# controller_left_upper.net
KiCad netlist of a schematic drawn in EAGLE
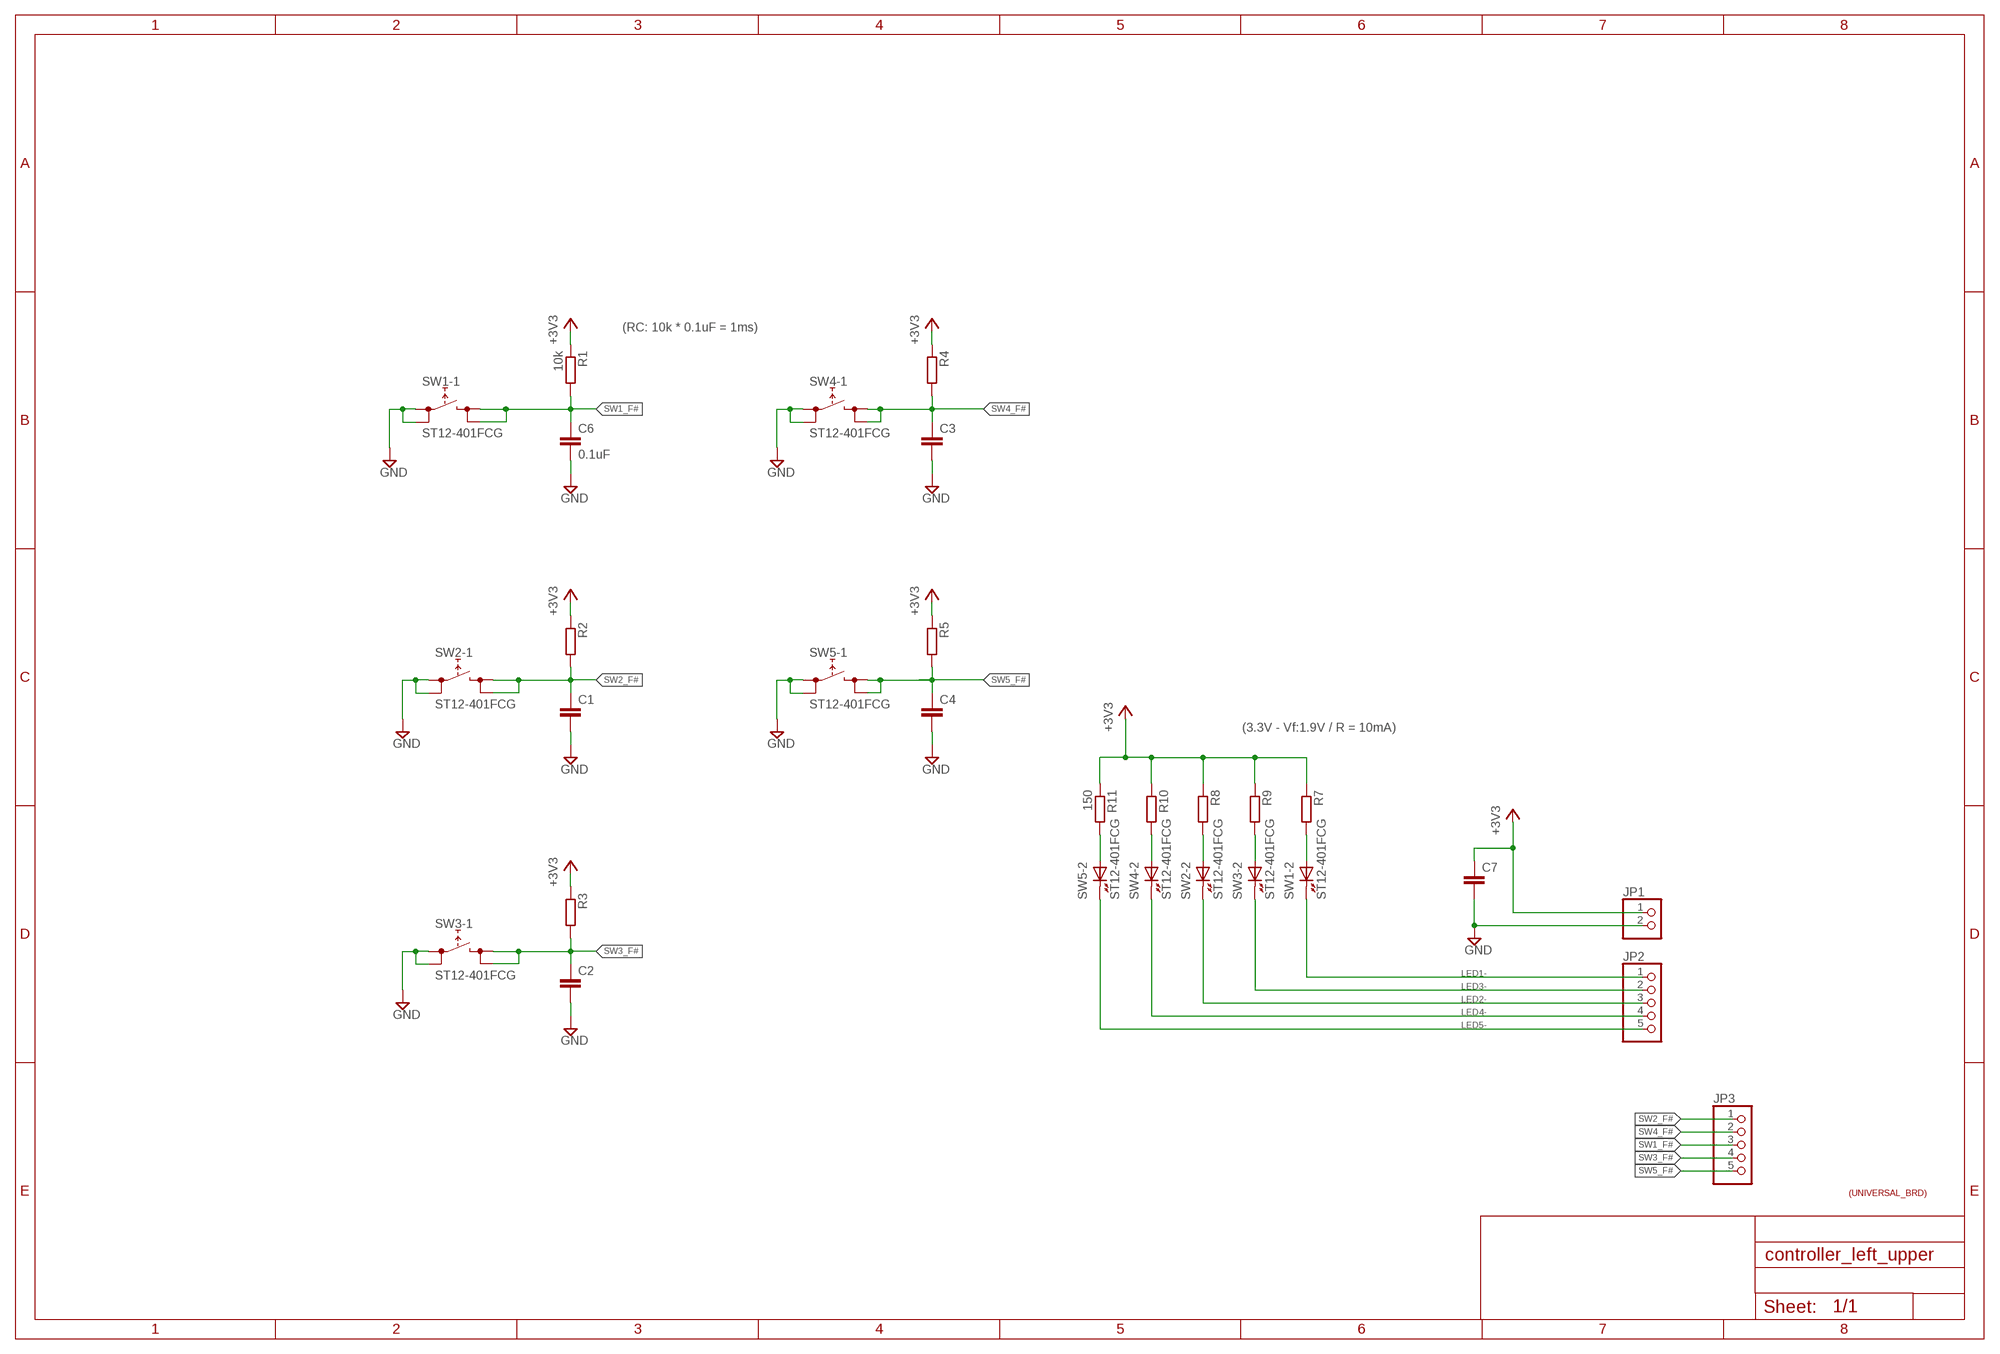
[diagram p0: schematic, sheet 1]

(export (version "E")
  (design (tool "Eeschema 10.0.6"))
  (components
    (comp (ref "C1")
      (value "C_DIP_2.54_1")
      (footprint "eagle-import:C_DIP2.54_1")
      (libsource (lib "eagle-import") (part "C_DIP_2.54_1"))
    )
    (comp (ref "C2")
      (value "C_DIP_2.54_1")
      (footprint "eagle-import:C_DIP2.54_1")
      (libsource (lib "eagle-import") (part "C_DIP_2.54_1"))
    )
    (comp (ref "C3")
      (value "C_DIP_2.54_1")
      (footprint "eagle-import:C_DIP2.54_1")
      (libsource (lib "eagle-import") (part "C_DIP_2.54_1"))
    )
    (comp (ref "C4")
      (value "C_DIP_2.54_1")
      (footprint "eagle-import:C_DIP2.54_1")
      (libsource (lib "eagle-import") (part "C_DIP_2.54_1"))
    )
    (comp (ref "C6")
      (value "0.1uF")
      (footprint "eagle-import:C_DIP2.54_1")
      (libsource (lib "eagle-import") (part "C_DIP_2.54_1"))
    )
    (comp (ref "C7")
      (value "C_DIP_2.54_1")
      (footprint "eagle-import:C_DIP2.54_1")
      (libsource (lib "eagle-import") (part "C_DIP_2.54_1"))
    )
    (comp (ref "JP1")
      (value "PINHD-1X2")
      (footprint "eagle-import:1X02")
      (libsource (lib "eagle-import") (part "PINHD-1X2"))
    )
    (comp (ref "JP2")
      (value "PINHD-1X5")
      (footprint "eagle-import:1X05")
      (libsource (lib "eagle-import") (part "PINHD-1X5"))
    )
    (comp (ref "JP3")
      (value "PINHD-1X5")
      (footprint "eagle-import:1X05")
      (libsource (lib "eagle-import") (part "PINHD-1X5"))
    )
    (comp (ref "R1")
      (value "10k")
      (footprint "eagle-import:R_DIP2.54_4")
      (libsource (lib "eagle-import") (part "R_DIP_4"))
    )
    (comp (ref "R2")
      (value "R_DIP_4")
      (footprint "eagle-import:R_DIP2.54_4")
      (libsource (lib "eagle-import") (part "R_DIP_4"))
    )
    (comp (ref "R3")
      (value "R_DIP_4")
      (footprint "eagle-import:R_DIP2.54_4")
      (libsource (lib "eagle-import") (part "R_DIP_4"))
    )
    (comp (ref "R4")
      (value "R_DIP_4")
      (footprint "eagle-import:R_DIP2.54_4")
      (libsource (lib "eagle-import") (part "R_DIP_4"))
    )
    (comp (ref "R5")
      (value "R_DIP_4")
      (footprint "eagle-import:R_DIP2.54_4")
      (libsource (lib "eagle-import") (part "R_DIP_4"))
    )
    (comp (ref "R7")
      (value "R_DIP_4")
      (footprint "eagle-import:R_DIP2.54_4")
      (libsource (lib "eagle-import") (part "R_DIP_4"))
    )
    (comp (ref "R8")
      (value "R_DIP_4")
      (footprint "eagle-import:R_DIP2.54_4")
      (libsource (lib "eagle-import") (part "R_DIP_4"))
    )
    (comp (ref "R9")
      (value "R_DIP_4")
      (footprint "eagle-import:R_DIP2.54_4")
      (libsource (lib "eagle-import") (part "R_DIP_4"))
    )
    (comp (ref "R10")
      (value "R_DIP_4")
      (footprint "eagle-import:R_DIP2.54_4")
      (libsource (lib "eagle-import") (part "R_DIP_4"))
    )
    (comp (ref "R11")
      (value "150")
      (footprint "eagle-import:R_DIP2.54_4")
      (libsource (lib "eagle-import") (part "R_DIP_4"))
    )
    (comp (ref "SW1")
      (value "ST12-401FCG")
      (footprint "eagle-import:ST12-401FCG")
      (libsource (lib "eagle-import") (part "ST12-401FCG"))
    )
    (comp (ref "SW2")
      (value "ST12-401FCG")
      (footprint "eagle-import:ST12-401FCG")
      (libsource (lib "eagle-import") (part "ST12-401FCG"))
    )
    (comp (ref "SW3")
      (value "ST12-401FCG")
      (footprint "eagle-import:ST12-401FCG")
      (libsource (lib "eagle-import") (part "ST12-401FCG"))
    )
    (comp (ref "SW4")
      (value "ST12-401FCG")
      (footprint "eagle-import:ST12-401FCG")
      (libsource (lib "eagle-import") (part "ST12-401FCG"))
    )
    (comp (ref "SW5")
      (value "ST12-401FCG")
      (footprint "eagle-import:ST12-401FCG")
      (libsource (lib "eagle-import") (part "ST12-401FCG"))
    )
    (comp (ref "U$1")
      (value "UNIVERSAL_BRD_95MM_72MM")
      (footprint "eagle-import:UNIVERSAL_BRD_95MM_72MM")
      (libsource (lib "eagle-import") (part "UNIVERSAL_BRD_95MM_72MM"))
    )
  )
  (nets
    (net (code "1") (name "+3V3") (class "Default")
      (node (ref "C7") (pin "1") (pinfunction "1_1") (pintype "passive"))
      (node (ref "JP1") (pin "1") (pinfunction "1_1") (pintype "passive"))
      (node (ref "R1") (pin "1") (pinfunction "1_1") (pintype "passive"))
      (node (ref "R10") (pin "1") (pinfunction "1_1") (pintype "passive"))
      (node (ref "R11") (pin "1") (pinfunction "1_1") (pintype "passive"))
      (node (ref "R2") (pin "1") (pinfunction "1_1") (pintype "passive"))
      (node (ref "R3") (pin "1") (pinfunction "1_1") (pintype "passive"))
      (node (ref "R4") (pin "1") (pinfunction "1_1") (pintype "passive"))
      (node (ref "R5") (pin "1") (pinfunction "1_1") (pintype "passive"))
      (node (ref "R7") (pin "1") (pinfunction "1_1") (pintype "passive"))
      (node (ref "R8") (pin "1") (pinfunction "1_1") (pintype "passive"))
      (node (ref "R9") (pin "1") (pinfunction "1_1") (pintype "passive"))
    )
    (net (code "2") (name "/LED1-") (class "Default")
      (node (ref "JP2") (pin "1") (pinfunction "1_1") (pintype "passive"))
      (node (ref "SW1") (pin "-") (pinfunction "K_-") (pintype "passive"))
    )
    (net (code "3") (name "/LED2-") (class "Default")
      (node (ref "JP2") (pin "3") (pinfunction "3_3") (pintype "passive"))
      (node (ref "SW2") (pin "-") (pinfunction "K_-") (pintype "passive"))
    )
    (net (code "4") (name "/LED3-") (class "Default")
      (node (ref "JP2") (pin "2") (pinfunction "2_2") (pintype "passive"))
      (node (ref "SW3") (pin "-") (pinfunction "K_-") (pintype "passive"))
    )
    (net (code "5") (name "/LED4-") (class "Default")
      (node (ref "JP2") (pin "4") (pinfunction "4_4") (pintype "passive"))
      (node (ref "SW4") (pin "-") (pinfunction "K_-") (pintype "passive"))
    )
    (net (code "6") (name "/LED5-") (class "Default")
      (node (ref "JP2") (pin "5") (pinfunction "5_5") (pintype "passive"))
      (node (ref "SW5") (pin "-") (pinfunction "K_-") (pintype "passive"))
    )
    (net (code "7") (name "GND") (class "Default")
      (node (ref "C1") (pin "2") (pinfunction "2_2") (pintype "passive"))
      (node (ref "C2") (pin "2") (pinfunction "2_2") (pintype "passive"))
      (node (ref "C3") (pin "2") (pinfunction "2_2") (pintype "passive"))
      (node (ref "C4") (pin "2") (pinfunction "2_2") (pintype "passive"))
      (node (ref "C6") (pin "2") (pinfunction "2_2") (pintype "passive"))
      (node (ref "C7") (pin "2") (pinfunction "2_2") (pintype "passive"))
      (node (ref "JP1") (pin "2") (pinfunction "2_2") (pintype "passive"))
      (node (ref "SW1") (pin "1") (pinfunction "0_1") (pintype "passive"))
      (node (ref "SW1") (pin "2") (pinfunction "0_2") (pintype "passive"))
      (node (ref "SW2") (pin "1") (pinfunction "0_1") (pintype "passive"))
      (node (ref "SW2") (pin "2") (pinfunction "0_2") (pintype "passive"))
      (node (ref "SW3") (pin "1") (pinfunction "0_1") (pintype "passive"))
      (node (ref "SW3") (pin "2") (pinfunction "0_2") (pintype "passive"))
      (node (ref "SW4") (pin "1") (pinfunction "0_1") (pintype "passive"))
      (node (ref "SW4") (pin "2") (pinfunction "0_2") (pintype "passive"))
      (node (ref "SW5") (pin "1") (pinfunction "0_1") (pintype "passive"))
      (node (ref "SW5") (pin "2") (pinfunction "0_2") (pintype "passive"))
    )
    (net (code "8") (name "Net-(SW1B-A)") (class "Default")
      (node (ref "R7") (pin "2") (pinfunction "2_2") (pintype "passive"))
      (node (ref "SW1") (pin "+") (pinfunction "A_+") (pintype "passive"))
    )
    (net (code "9") (name "Net-(SW2B-A)") (class "Default")
      (node (ref "R8") (pin "2") (pinfunction "2_2") (pintype "passive"))
      (node (ref "SW2") (pin "+") (pinfunction "A_+") (pintype "passive"))
    )
    (net (code "10") (name "Net-(SW3B-A)") (class "Default")
      (node (ref "R9") (pin "2") (pinfunction "2_2") (pintype "passive"))
      (node (ref "SW3") (pin "+") (pinfunction "A_+") (pintype "passive"))
    )
    (net (code "11") (name "Net-(SW4B-A)") (class "Default")
      (node (ref "R10") (pin "2") (pinfunction "2_2") (pintype "passive"))
      (node (ref "SW4") (pin "+") (pinfunction "A_+") (pintype "passive"))
    )
    (net (code "12") (name "Net-(SW5B-A)") (class "Default")
      (node (ref "R11") (pin "2") (pinfunction "2_2") (pintype "passive"))
      (node (ref "SW5") (pin "+") (pinfunction "A_+") (pintype "passive"))
    )
    (net (code "13") (name "SW1_F#") (class "Default")
      (node (ref "C6") (pin "1") (pinfunction "1_1") (pintype "passive"))
      (node (ref "JP3") (pin "3") (pinfunction "3_3") (pintype "passive"))
      (node (ref "R1") (pin "2") (pinfunction "2_2") (pintype "passive"))
      (node (ref "SW1") (pin "3") (pinfunction "1_3") (pintype "passive"))
      (node (ref "SW1") (pin "4") (pinfunction "1_4") (pintype "passive"))
    )
    (net (code "14") (name "SW2_F#") (class "Default")
      (node (ref "C1") (pin "1") (pinfunction "1_1") (pintype "passive"))
      (node (ref "JP3") (pin "1") (pinfunction "1_1") (pintype "passive"))
      (node (ref "R2") (pin "2") (pinfunction "2_2") (pintype "passive"))
      (node (ref "SW2") (pin "3") (pinfunction "1_3") (pintype "passive"))
      (node (ref "SW2") (pin "4") (pinfunction "1_4") (pintype "passive"))
    )
    (net (code "15") (name "SW3_F#") (class "Default")
      (node (ref "C2") (pin "1") (pinfunction "1_1") (pintype "passive"))
      (node (ref "JP3") (pin "4") (pinfunction "4_4") (pintype "passive"))
      (node (ref "R3") (pin "2") (pinfunction "2_2") (pintype "passive"))
      (node (ref "SW3") (pin "3") (pinfunction "1_3") (pintype "passive"))
      (node (ref "SW3") (pin "4") (pinfunction "1_4") (pintype "passive"))
    )
    (net (code "16") (name "SW4_F#") (class "Default")
      (node (ref "C3") (pin "1") (pinfunction "1_1") (pintype "passive"))
      (node (ref "JP3") (pin "2") (pinfunction "2_2") (pintype "passive"))
      (node (ref "R4") (pin "2") (pinfunction "2_2") (pintype "passive"))
      (node (ref "SW4") (pin "3") (pinfunction "1_3") (pintype "passive"))
      (node (ref "SW4") (pin "4") (pinfunction "1_4") (pintype "passive"))
    )
    (net (code "17") (name "SW5_F#") (class "Default")
      (node (ref "C4") (pin "1") (pinfunction "1_1") (pintype "passive"))
      (node (ref "JP3") (pin "5") (pinfunction "5_5") (pintype "passive"))
      (node (ref "R5") (pin "2") (pinfunction "2_2") (pintype "passive"))
      (node (ref "SW5") (pin "3") (pinfunction "1_3") (pintype "passive"))
      (node (ref "SW5") (pin "4") (pinfunction "1_4") (pintype "passive"))
    )
  )
)
